# Pi_grammer_SERIAL_UPLOAD_ADD_ON.net
KiCad netlist of a schematic drawn in EAGLE
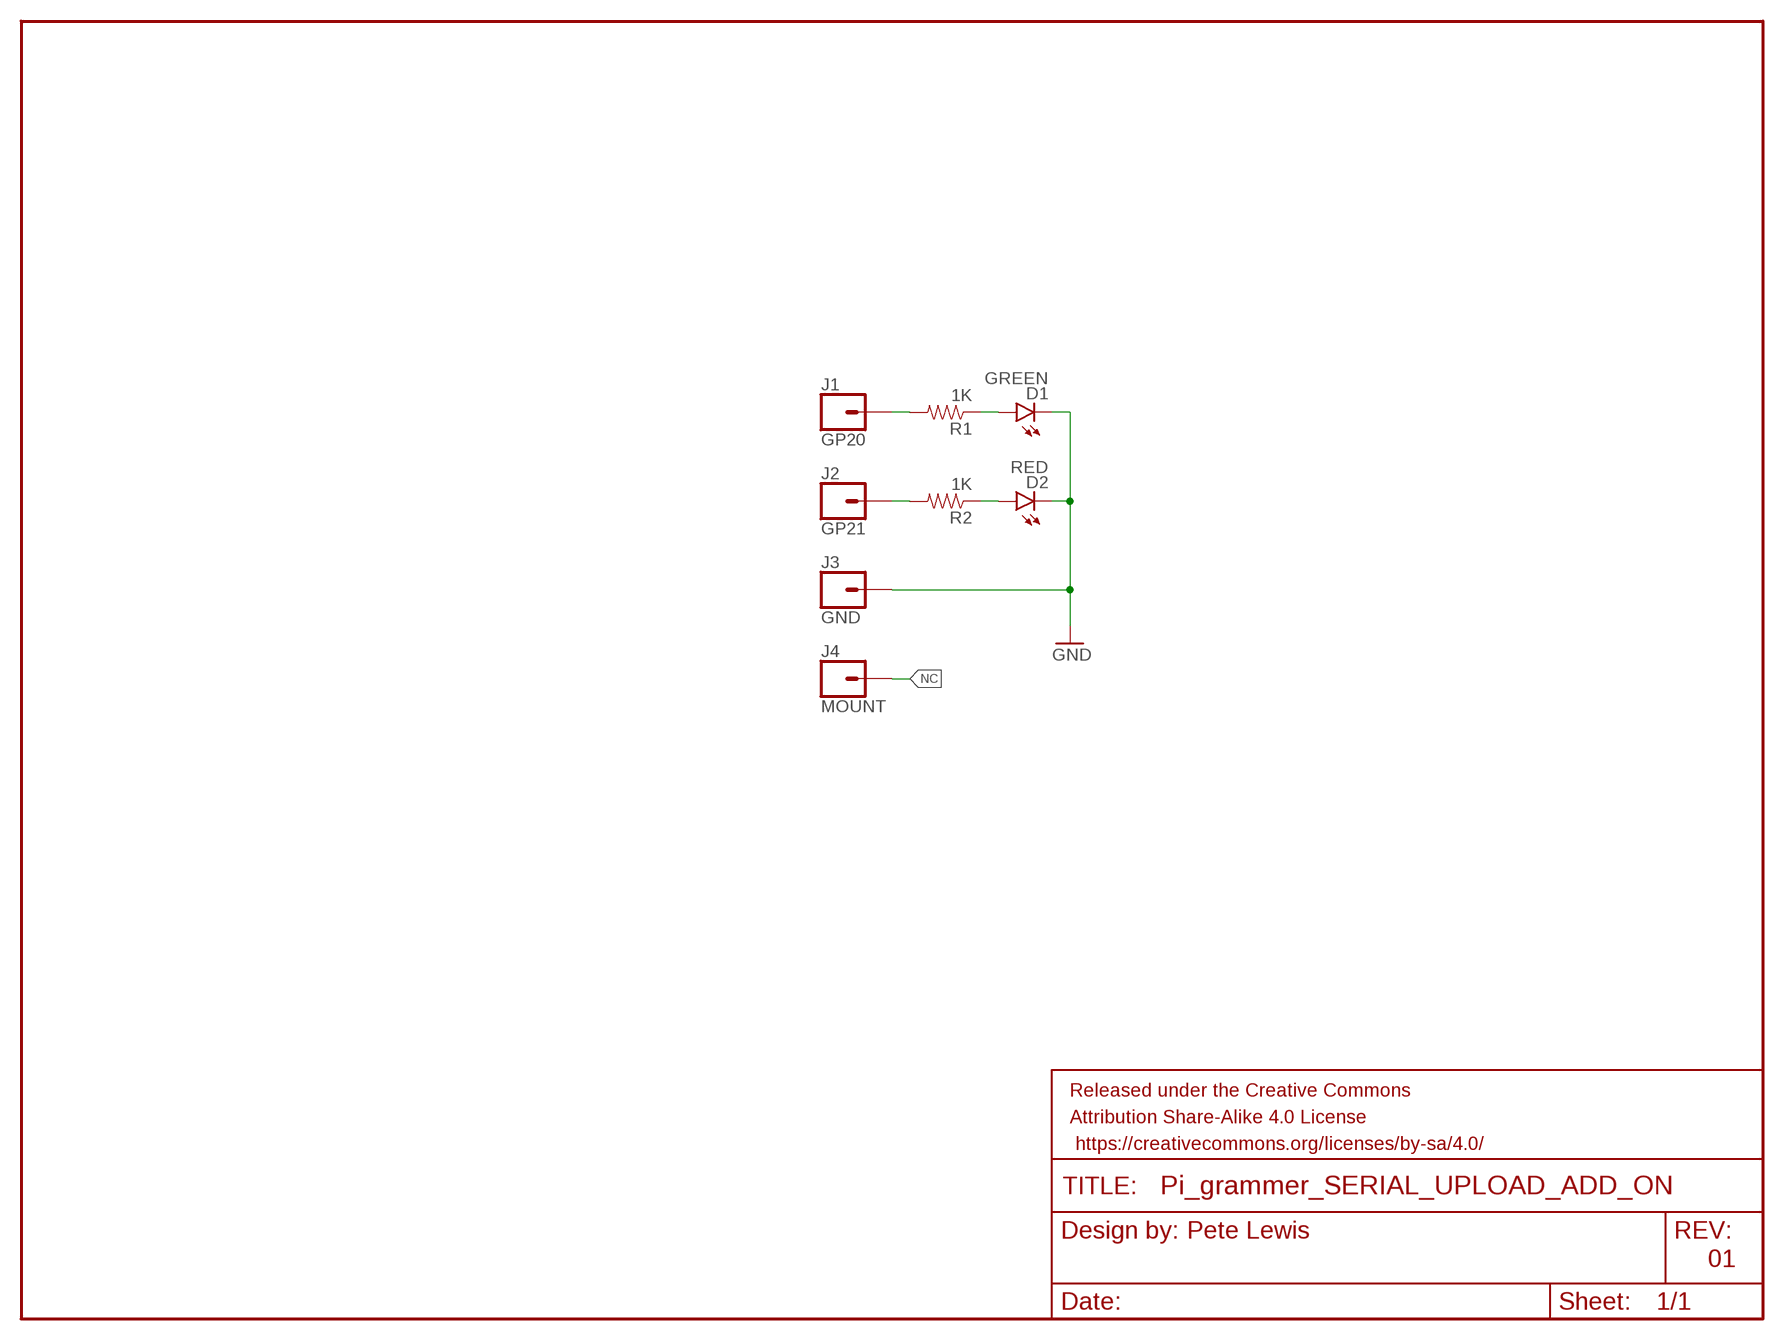
[diagram p0: schematic, sheet 1]

(export (version "E")
  (design (tool "Eeschema 10.0.6"))
  (components
    (comp (ref "D1")
      (value "GREEN")
      (footprint "eagle-import:LED-1206")
      (libsource (lib "eagle-import") (part "LED-GREEN1206"))
    )
    (comp (ref "D2")
      (value "RED")
      (footprint "eagle-import:LED-1206")
      (libsource (lib "eagle-import") (part "LED-RED1206"))
    )
    (comp (ref "FRAME1")
      (value "FRAME-LETTER")
      (footprint "eagle-import:CREATIVE_COMMONS")
      (libsource (lib "eagle-import") (part "FRAME-LETTER"))
    )
    (comp (ref "J1")
      (value "GP20")
      (footprint "eagle-import:1X01")
      (libsource (lib "eagle-import") (part "CONN_01"))
    )
    (comp (ref "J2")
      (value "GP21")
      (footprint "eagle-import:1X01")
      (libsource (lib "eagle-import") (part "CONN_01"))
    )
    (comp (ref "J3")
      (value "GND")
      (footprint "eagle-import:1X01")
      (libsource (lib "eagle-import") (part "CONN_01"))
    )
    (comp (ref "J4")
      (value "MOUNT")
      (footprint "eagle-import:1X01")
      (libsource (lib "eagle-import") (part "CONN_01"))
    )
    (comp (ref "R1")
      (value "1K")
      (footprint "eagle-import:0603-RES")
      (libsource (lib "eagle-import") (part "1KOHM-1/10W-1%(0603)"))
    )
    (comp (ref "R2")
      (value "1K")
      (footprint "eagle-import:0603-RES")
      (libsource (lib "eagle-import") (part "1KOHM-1/10W-1%(0603)"))
    )
  )
  (nets
    (net (code "1") (name "GND") (class "Default")
      (node (ref "D1") (pin "C") (pinfunction "C_C") (pintype "passive"))
      (node (ref "D2") (pin "C") (pinfunction "C_C") (pintype "passive"))
      (node (ref "J3") (pin "1") (pinfunction "1_1") (pintype "passive"))
    )
    (net (code "2") (name "NC") (class "Default")
      (node (ref "J4") (pin "1") (pinfunction "1_1") (pintype "passive"))
    )
    (net (code "3") (name "Net-(D1-PadA)") (class "Default")
      (node (ref "D1") (pin "A") (pinfunction "A_A") (pintype "passive"))
      (node (ref "R1") (pin "1") (pinfunction "1_1") (pintype "passive"))
    )
    (net (code "4") (name "Net-(D2-PadA)") (class "Default")
      (node (ref "D2") (pin "A") (pinfunction "A_A") (pintype "passive"))
      (node (ref "R2") (pin "1") (pinfunction "1_1") (pintype "passive"))
    )
    (net (code "5") (name "Net-(J1-Pad1)") (class "Default")
      (node (ref "J1") (pin "1") (pinfunction "1_1") (pintype "passive"))
      (node (ref "R1") (pin "2") (pinfunction "2_2") (pintype "passive"))
    )
    (net (code "6") (name "Net-(J2-Pad1)") (class "Default")
      (node (ref "J2") (pin "1") (pinfunction "1_1") (pintype "passive"))
      (node (ref "R2") (pin "2") (pinfunction "2_2") (pintype "passive"))
    )
  )
)
